# kinks_v41.net
KiCad netlist of a schematic drawn in EAGLE
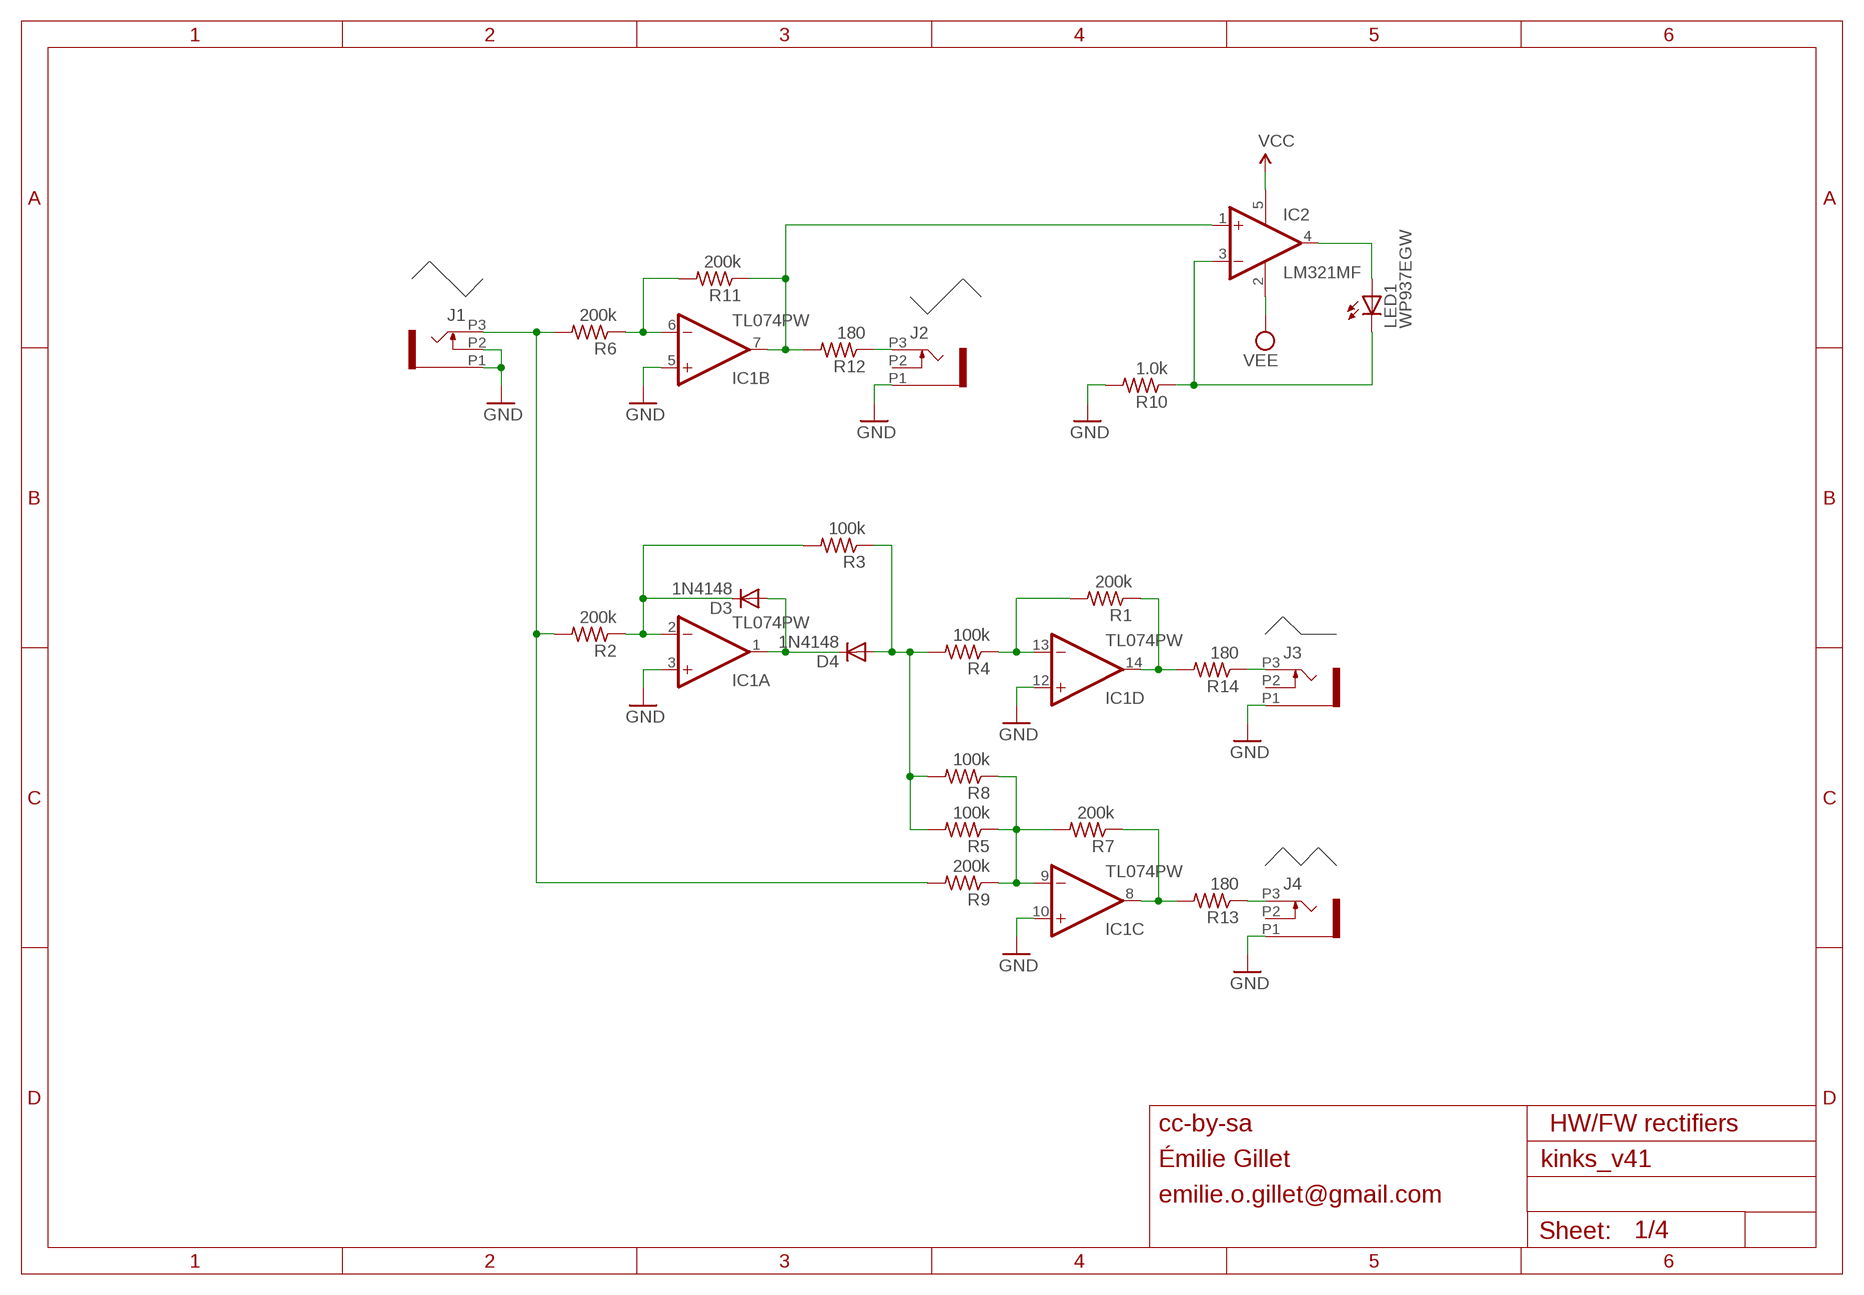
[diagram p0: schematic, sheet 1]
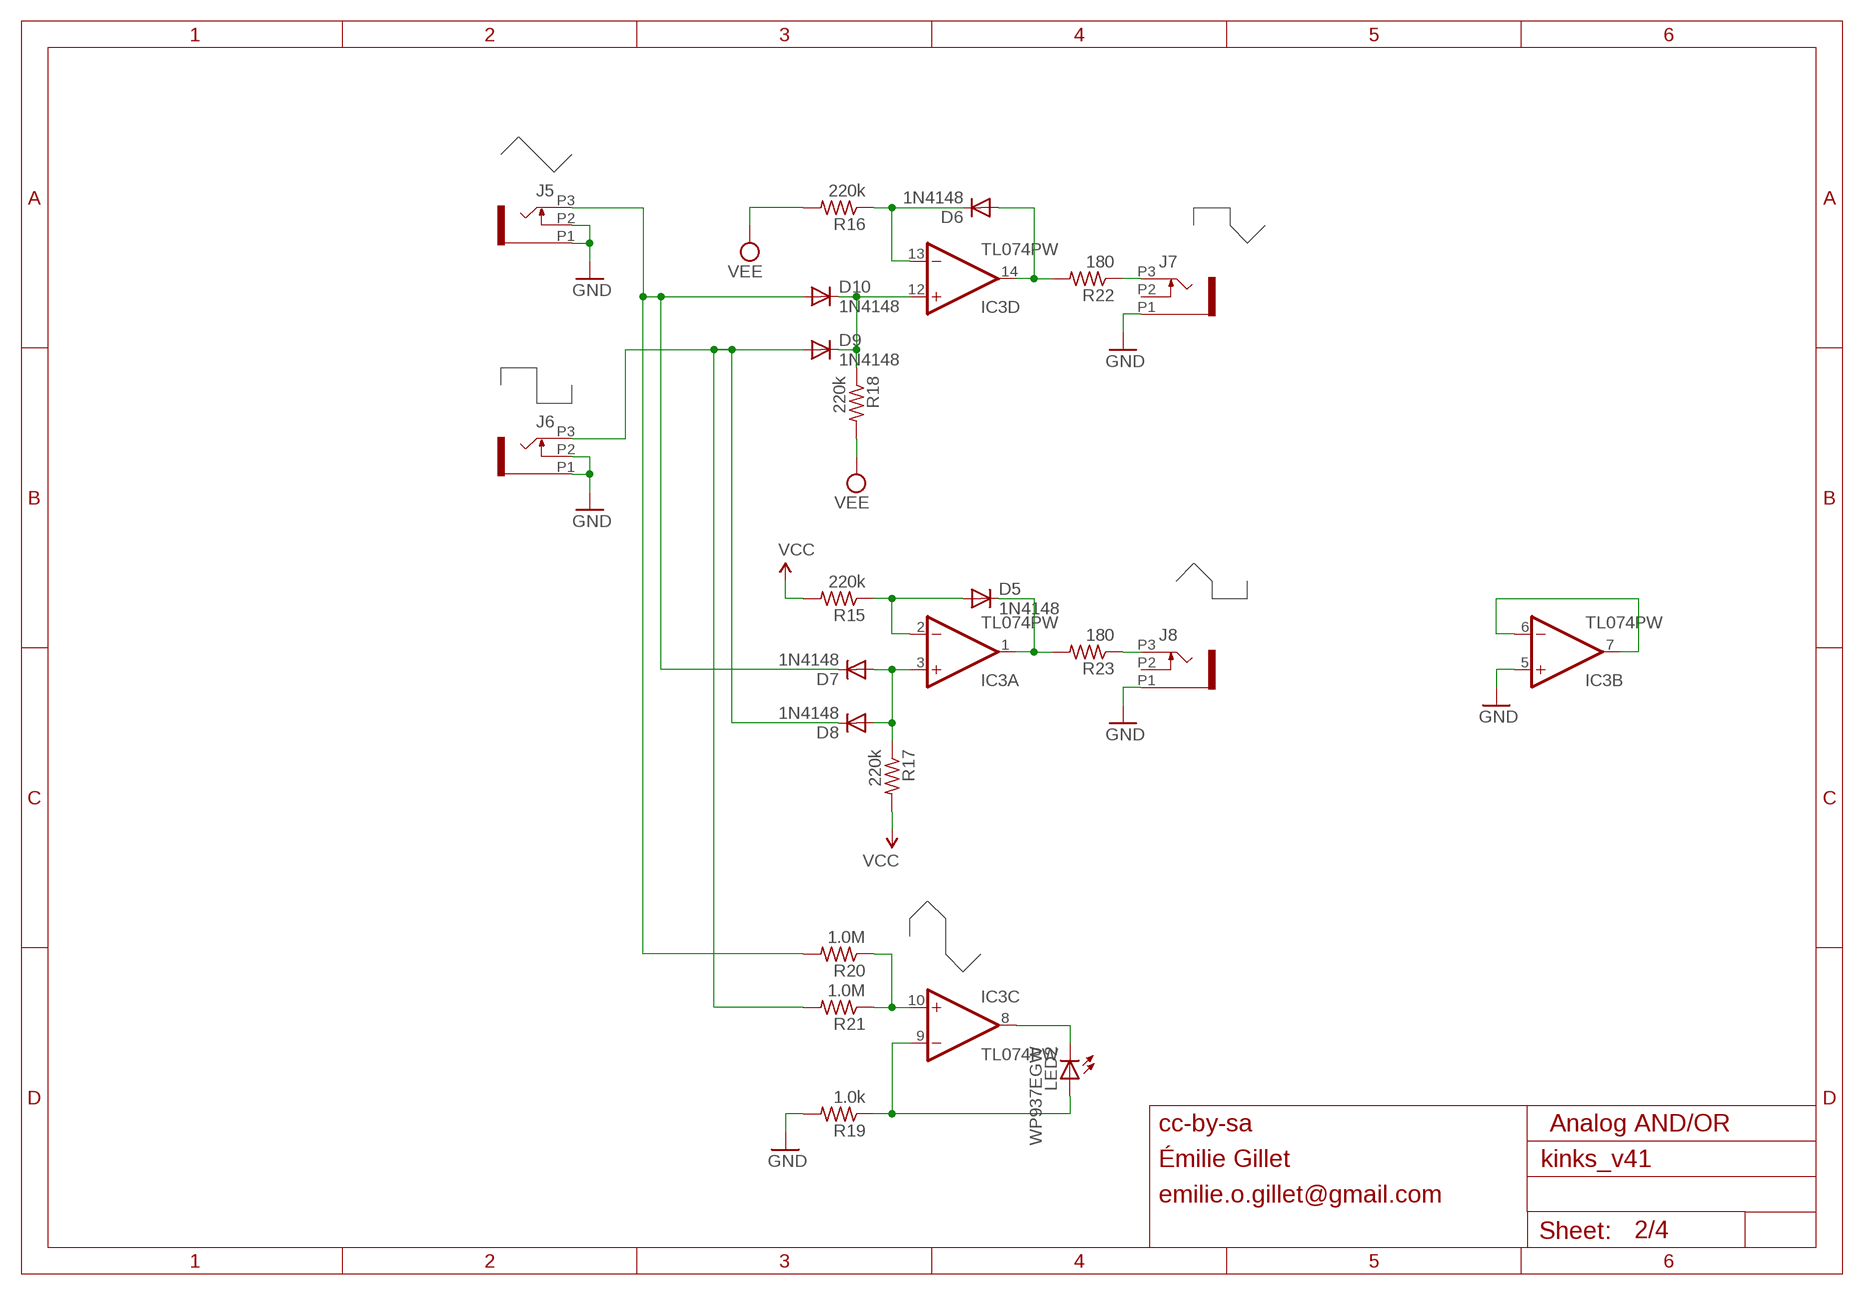
[diagram p1: schematic, sheet 2]
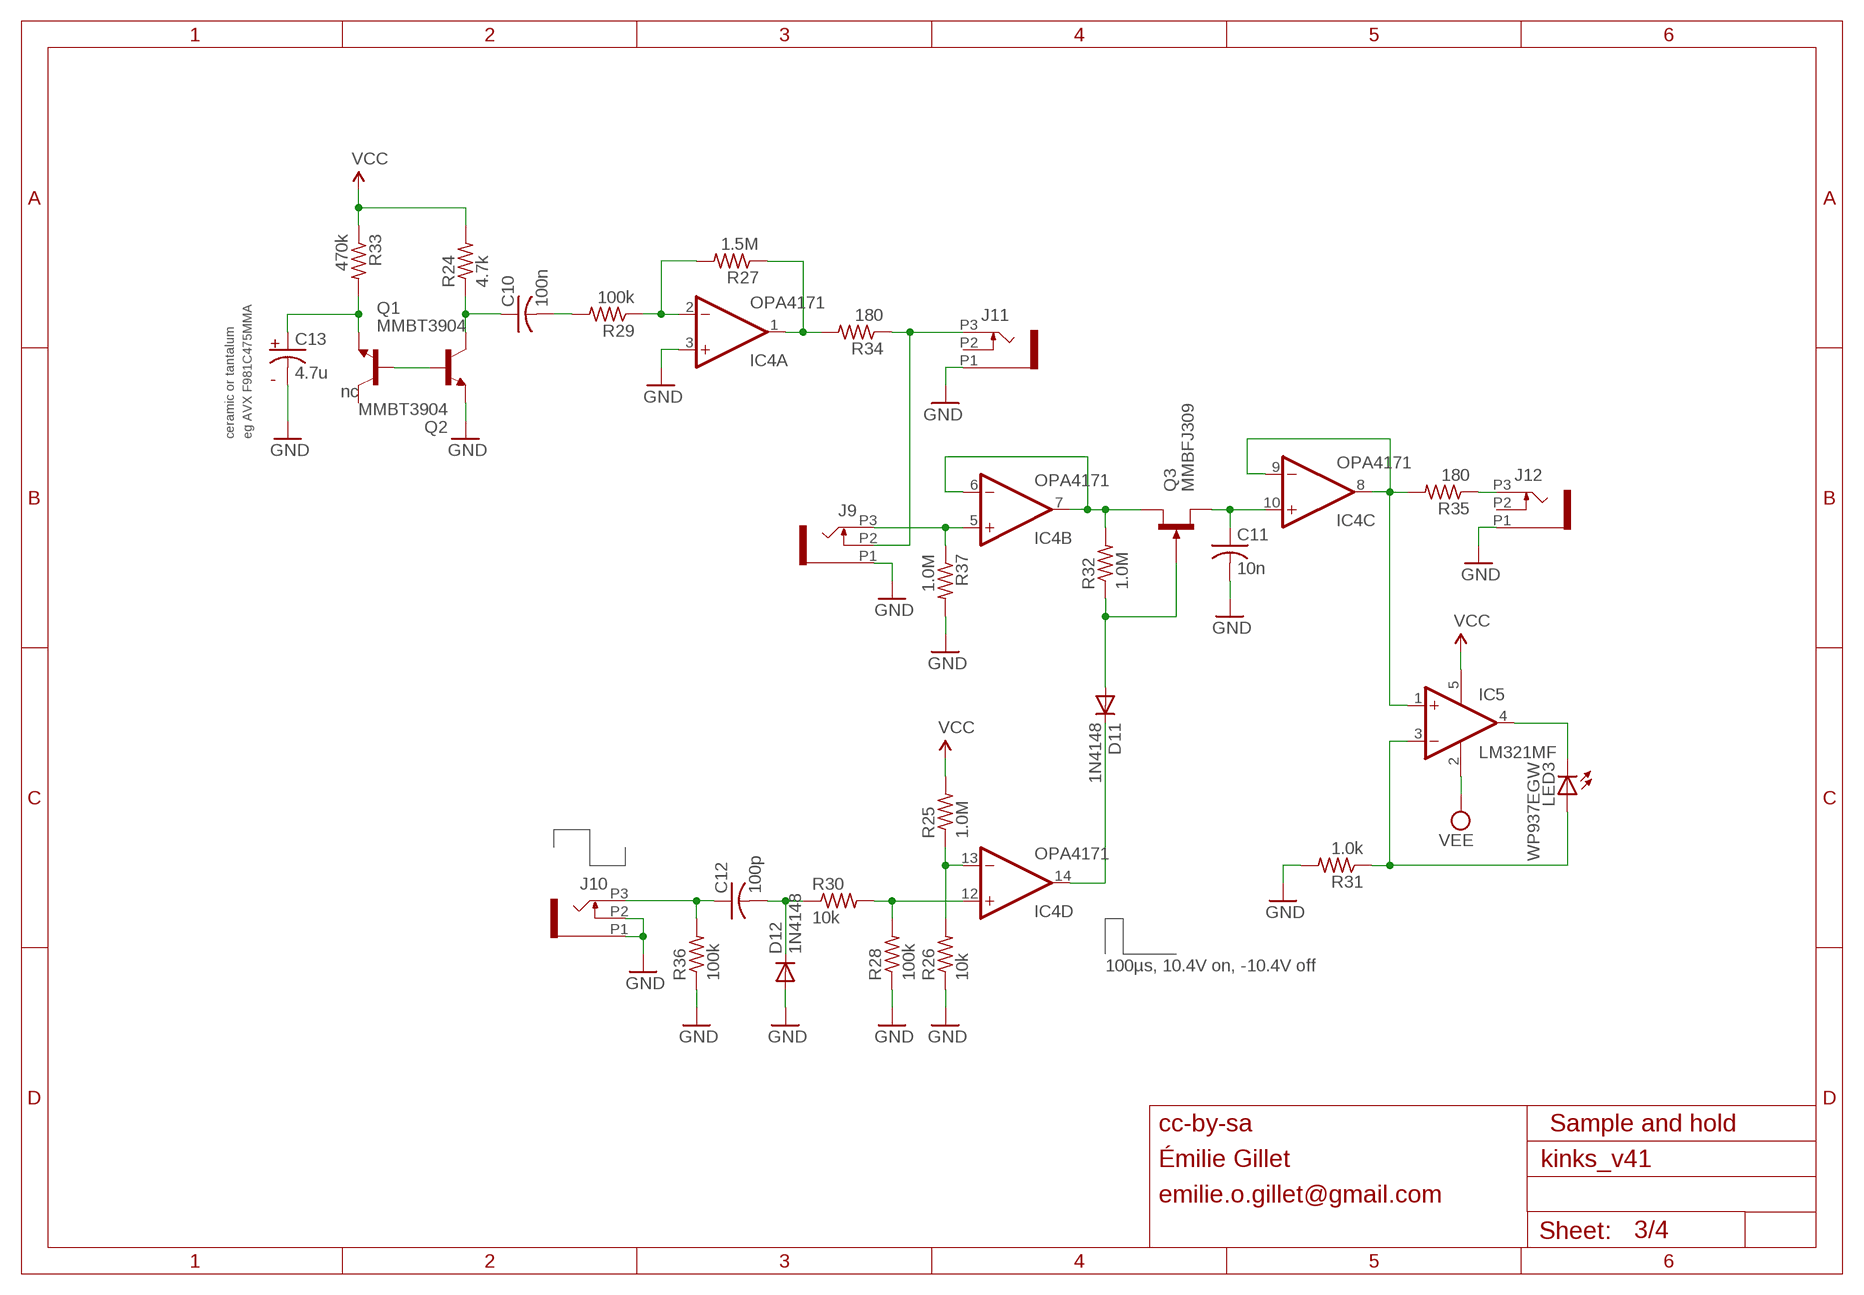
[diagram p2: schematic, sheet 3]
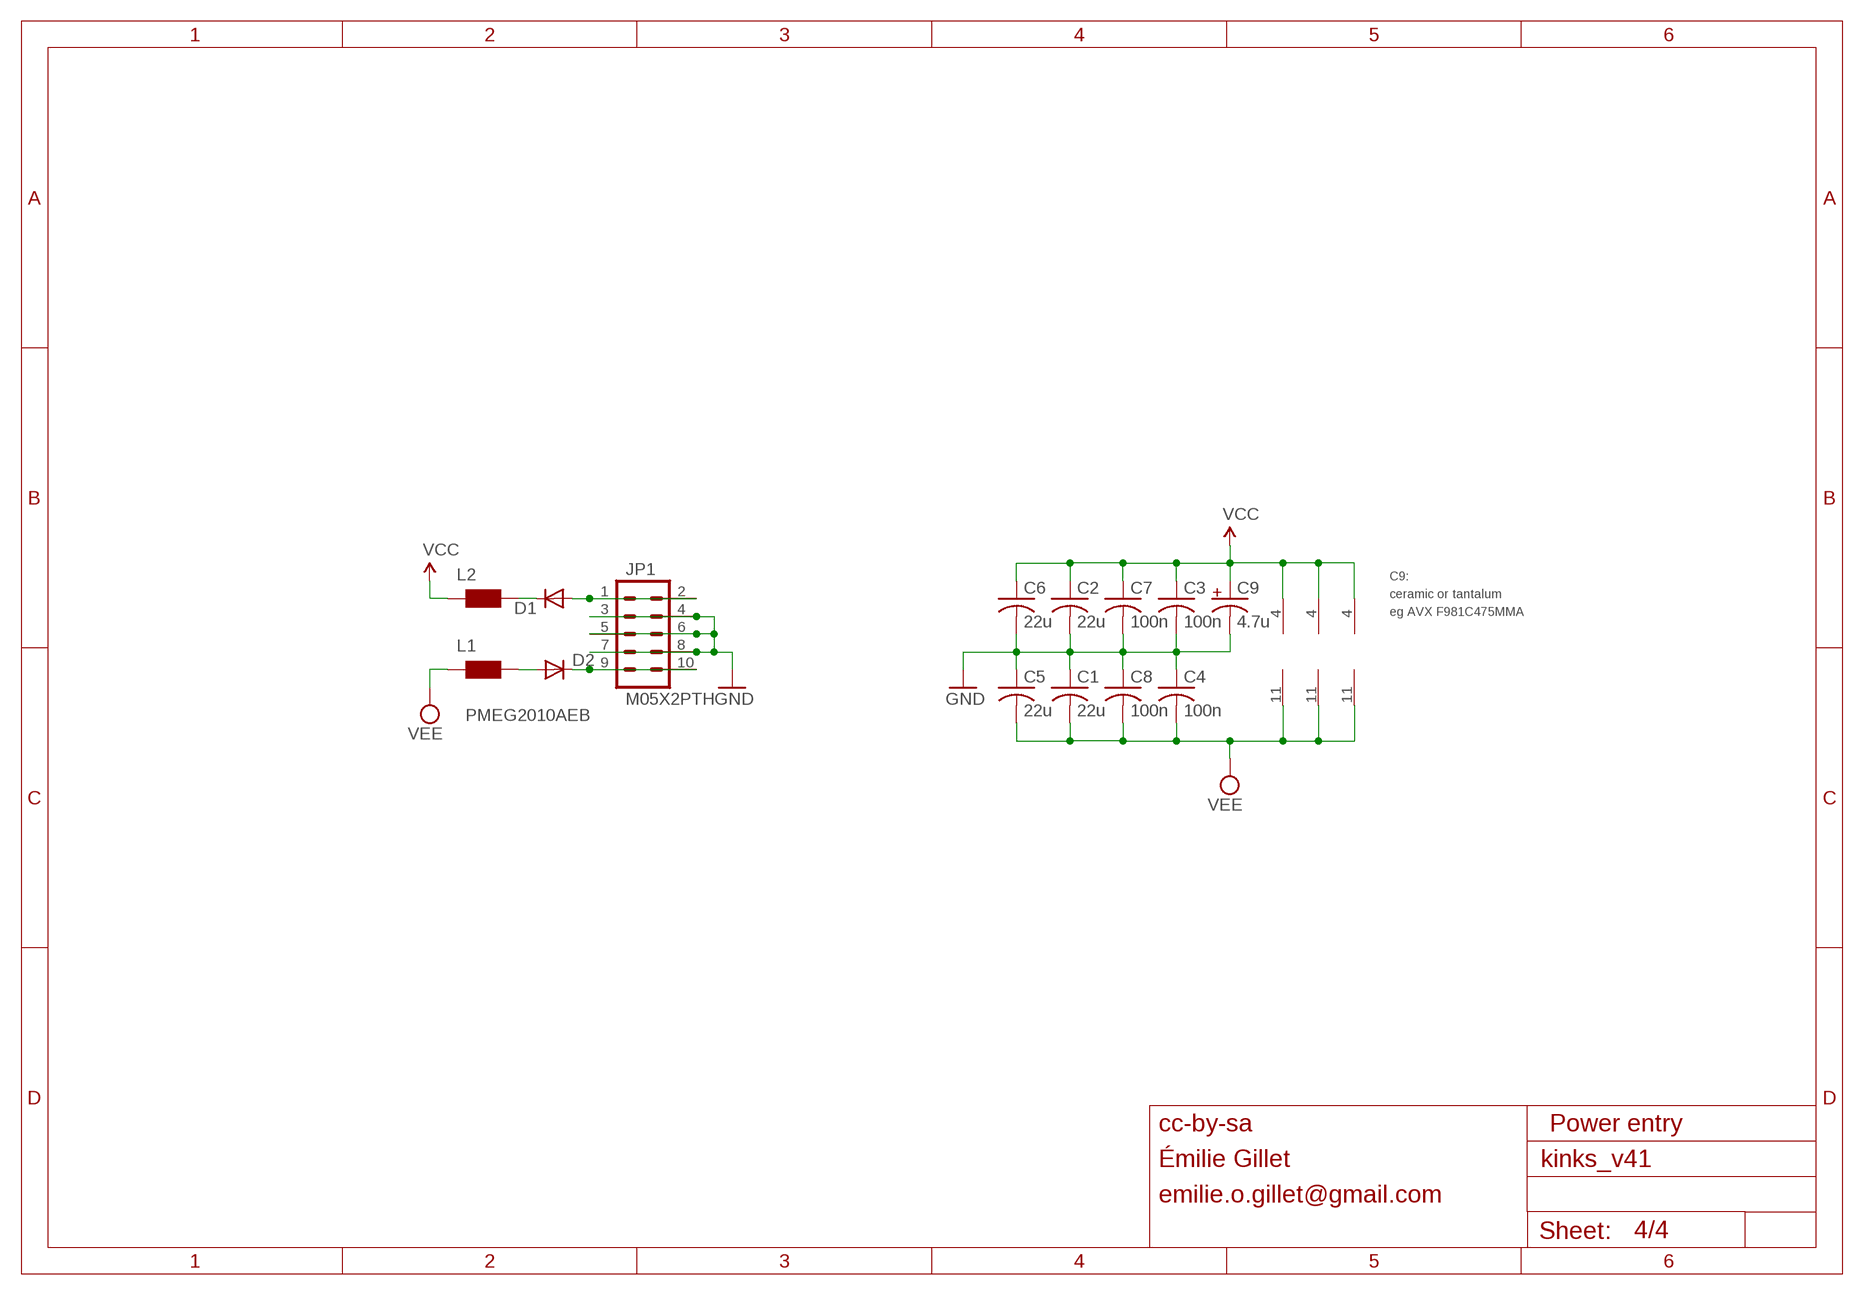
[diagram p3: schematic, sheet 4]

(export (version "E")
  (design (tool "Eeschema 10.0.6"))
  (components
    (comp (ref "D5")
      (value "1N4148")
      (footprint "eagle-import:SOD523")
      (libsource (lib "eagle-import") (part "DIODE-SOD523"))
    )
    (comp (ref "D6")
      (value "1N4148")
      (footprint "eagle-import:SOD523")
      (libsource (lib "eagle-import") (part "DIODE-SOD523"))
    )
    (comp (ref "D7")
      (value "1N4148")
      (footprint "eagle-import:SOD523")
      (libsource (lib "eagle-import") (part "DIODE-SOD523"))
    )
    (comp (ref "D8")
      (value "1N4148")
      (footprint "eagle-import:SOD523")
      (libsource (lib "eagle-import") (part "DIODE-SOD523"))
    )
    (comp (ref "D9")
      (value "1N4148")
      (footprint "eagle-import:SOD523")
      (libsource (lib "eagle-import") (part "DIODE-SOD523"))
    )
    (comp (ref "D10")
      (value "1N4148")
      (footprint "eagle-import:SOD523")
      (libsource (lib "eagle-import") (part "DIODE-SOD523"))
    )
    (comp (ref "IC3")
      (value "TL074PW")
      (footprint "eagle-import:TSSOP14")
      (libsource (lib "eagle-import") (part "TL074PW"))
    )
    (comp (ref "J5")
      (value "PJ301_THONKICONN6")
      (footprint "eagle-import:WQP_PJ_301M6")
      (libsource (lib "eagle-import") (part "PJ301_THONKICONN6"))
    )
    (comp (ref "J6")
      (value "PJ301_THONKICONN6")
      (footprint "eagle-import:WQP_PJ_301M6")
      (libsource (lib "eagle-import") (part "PJ301_THONKICONN6"))
    )
    (comp (ref "J7")
      (value "PJ301_THONKICONN6")
      (footprint "eagle-import:WQP_PJ_301M6")
      (libsource (lib "eagle-import") (part "PJ301_THONKICONN6"))
    )
    (comp (ref "J8")
      (value "PJ301_THONKICONN6")
      (footprint "eagle-import:WQP_PJ_301M6")
      (libsource (lib "eagle-import") (part "PJ301_THONKICONN6"))
    )
    (comp (ref "LED2")
      (value "WP937EGW")
      (footprint "eagle-import:LED3MM")
      (libsource (lib "eagle-import") (part "LED3MM"))
    )
    (comp (ref "R15")
      (value "220k")
      (footprint "eagle-import:R0402")
      (libsource (lib "eagle-import") (part "R-US_R0402"))
    )
    (comp (ref "R16")
      (value "220k")
      (footprint "eagle-import:R0402")
      (libsource (lib "eagle-import") (part "R-US_R0402"))
    )
    (comp (ref "R17")
      (value "220k")
      (footprint "eagle-import:R0402")
      (libsource (lib "eagle-import") (part "R-US_R0402"))
    )
    (comp (ref "R18")
      (value "220k")
      (footprint "eagle-import:R0402")
      (libsource (lib "eagle-import") (part "R-US_R0402"))
    )
    (comp (ref "R19")
      (value "1.0k")
      (footprint "eagle-import:R0402")
      (libsource (lib "eagle-import") (part "R-US_R0402"))
    )
    (comp (ref "R20")
      (value "1.0M")
      (footprint "eagle-import:R0402")
      (libsource (lib "eagle-import") (part "R-US_R0402"))
    )
    (comp (ref "R21")
      (value "1.0M")
      (footprint "eagle-import:R0402")
      (libsource (lib "eagle-import") (part "R-US_R0402"))
    )
    (comp (ref "R22")
      (value "180")
      (footprint "eagle-import:R0402")
      (libsource (lib "eagle-import") (part "R-US_R0402"))
    )
    (comp (ref "R23")
      (value "180")
      (footprint "eagle-import:R0402")
      (libsource (lib "eagle-import") (part "R-US_R0402"))
    )
    (comp (ref "C1")
      (value "22u")
      (footprint "eagle-import:C0805")
      (libsource (lib "eagle-import") (part "C-USC0805"))
    )
    (comp (ref "C2")
      (value "22u")
      (footprint "eagle-import:C0805")
      (libsource (lib "eagle-import") (part "C-USC0805"))
    )
    (comp (ref "C3")
      (value "100n")
      (footprint "eagle-import:C0402")
      (libsource (lib "eagle-import") (part "C-USC0402"))
    )
    (comp (ref "C4")
      (value "100n")
      (footprint "eagle-import:C0402")
      (libsource (lib "eagle-import") (part "C-USC0402"))
    )
    (comp (ref "C5")
      (value "22u")
      (footprint "eagle-import:C0805")
      (libsource (lib "eagle-import") (part "C-USC0805"))
    )
    (comp (ref "C6")
      (value "22u")
      (footprint "eagle-import:C0805")
      (libsource (lib "eagle-import") (part "C-USC0805"))
    )
    (comp (ref "C7")
      (value "100n")
      (footprint "eagle-import:C0402")
      (libsource (lib "eagle-import") (part "C-USC0402"))
    )
    (comp (ref "C8")
      (value "100n")
      (footprint "eagle-import:C0402")
      (libsource (lib "eagle-import") (part "C-USC0402"))
    )
    (comp (ref "C9")
      (value "4.7u")
      (footprint "eagle-import:C0603")
      (libsource (lib "eagle-import") (part "C-USC0603"))
    )
    (comp (ref "D1")
      (value "PMEG2010AEB")
      (footprint "eagle-import:SOD523")
      (libsource (lib "eagle-import") (part "DIODE-SOD523"))
    )
    (comp (ref "D2")
      (value "PMEG2010AEB")
      (footprint "eagle-import:SOD523")
      (libsource (lib "eagle-import") (part "DIODE-SOD523"))
    )
    (comp (ref "IC1")
      (value "TL074PW")
      (footprint "eagle-import:TSSOP14")
      (libsource (lib "eagle-import") (part "TL074PW"))
    )
    (comp (ref "IC4")
      (value "OPA4171")
      (footprint "eagle-import:TSSOP14")
      (libsource (lib "eagle-import") (part "TL074PW"))
    )
    (comp (ref "JP1")
      (value "M05X2PTH")
      (footprint "eagle-import:AVR_ICSP")
      (libsource (lib "eagle-import") (part "M05X2PTH"))
    )
    (comp (ref "L1")
      (value "WE-CBF_0603")
      (footprint "eagle-import:0603")
      (libsource (lib "eagle-import") (part "WE-CBF_0603"))
    )
    (comp (ref "L2")
      (value "WE-CBF_0603")
      (footprint "eagle-import:0603")
      (libsource (lib "eagle-import") (part "WE-CBF_0603"))
    )
    (comp (ref "D3")
      (value "1N4148")
      (footprint "eagle-import:SOD523")
      (libsource (lib "eagle-import") (part "DIODE-SOD523"))
    )
    (comp (ref "D4")
      (value "1N4148")
      (footprint "eagle-import:SOD523")
      (libsource (lib "eagle-import") (part "DIODE-SOD523"))
    )
    (comp (ref "IC2")
      (value "LM321MF")
      (footprint "eagle-import:SOT23-5")
      (libsource (lib "eagle-import") (part "LM321?MF"))
    )
    (comp (ref "J1")
      (value "PJ301_THONKICONN6")
      (footprint "eagle-import:WQP_PJ_301M6")
      (libsource (lib "eagle-import") (part "PJ301_THONKICONN6"))
    )
    (comp (ref "J2")
      (value "PJ301_THONKICONN6")
      (footprint "eagle-import:WQP_PJ_301M6")
      (libsource (lib "eagle-import") (part "PJ301_THONKICONN6"))
    )
    (comp (ref "J3")
      (value "PJ301_THONKICONN6")
      (footprint "eagle-import:WQP_PJ_301M6")
      (libsource (lib "eagle-import") (part "PJ301_THONKICONN6"))
    )
    (comp (ref "J4")
      (value "PJ301_THONKICONN6")
      (footprint "eagle-import:WQP_PJ_301M6")
      (libsource (lib "eagle-import") (part "PJ301_THONKICONN6"))
    )
    (comp (ref "LED1")
      (value "WP937EGW")
      (footprint "eagle-import:LED3MM")
      (libsource (lib "eagle-import") (part "LED3MM"))
    )
    (comp (ref "R1")
      (value "200k")
      (footprint "eagle-import:R0402")
      (libsource (lib "eagle-import") (part "R-US_R0402"))
    )
    (comp (ref "R2")
      (value "200k")
      (footprint "eagle-import:R0402")
      (libsource (lib "eagle-import") (part "R-US_R0402"))
    )
    (comp (ref "R3")
      (value "100k")
      (footprint "eagle-import:R0402")
      (libsource (lib "eagle-import") (part "R-US_R0402"))
    )
    (comp (ref "R4")
      (value "100k")
      (footprint "eagle-import:R0402")
      (libsource (lib "eagle-import") (part "R-US_R0402"))
    )
    (comp (ref "R5")
      (value "100k")
      (footprint "eagle-import:R0402")
      (libsource (lib "eagle-import") (part "R-US_R0402"))
    )
    (comp (ref "R6")
      (value "200k")
      (footprint "eagle-import:R0402")
      (libsource (lib "eagle-import") (part "R-US_R0402"))
    )
    (comp (ref "R7")
      (value "200k")
      (footprint "eagle-import:R0402")
      (libsource (lib "eagle-import") (part "R-US_R0402"))
    )
    (comp (ref "R8")
      (value "100k")
      (footprint "eagle-import:R0402")
      (libsource (lib "eagle-import") (part "R-US_R0402"))
    )
    (comp (ref "R9")
      (value "200k")
      (footprint "eagle-import:R0402")
      (libsource (lib "eagle-import") (part "R-US_R0402"))
    )
    (comp (ref "R10")
      (value "1.0k")
      (footprint "eagle-import:R0402")
      (libsource (lib "eagle-import") (part "R-US_R0402"))
    )
    (comp (ref "R11")
      (value "200k")
      (footprint "eagle-import:R0402")
      (libsource (lib "eagle-import") (part "R-US_R0402"))
    )
    (comp (ref "R12")
      (value "180")
      (footprint "eagle-import:R0402")
      (libsource (lib "eagle-import") (part "R-US_R0402"))
    )
    (comp (ref "R13")
      (value "180")
      (footprint "eagle-import:R0402")
      (libsource (lib "eagle-import") (part "R-US_R0402"))
    )
    (comp (ref "R14")
      (value "180")
      (footprint "eagle-import:R0402")
      (libsource (lib "eagle-import") (part "R-US_R0402"))
    )
    (comp (ref "C10")
      (value "100n")
      (footprint "eagle-import:C0402")
      (libsource (lib "eagle-import") (part "C-USC0402"))
    )
    (comp (ref "C11")
      (value "10n")
      (footprint "eagle-import:C0603")
      (libsource (lib "eagle-import") (part "C-USC0603"))
    )
    (comp (ref "C12")
      (value "100p")
      (footprint "eagle-import:C0402")
      (libsource (lib "eagle-import") (part "C-USC0402"))
    )
    (comp (ref "C13")
      (value "4.7u")
      (footprint "eagle-import:C0603")
      (libsource (lib "eagle-import") (part "C-USC0603"))
    )
    (comp (ref "D11")
      (value "1N4148")
      (footprint "eagle-import:SOD523")
      (libsource (lib "eagle-import") (part "DIODE-SOD523"))
    )
    (comp (ref "D12")
      (value "1N4148")
      (footprint "eagle-import:SOD523")
      (libsource (lib "eagle-import") (part "DIODE-SOD523"))
    )
    (comp (ref "IC5")
      (value "LM321MF")
      (footprint "eagle-import:SOT23-5")
      (libsource (lib "eagle-import") (part "LM321?MF"))
    )
    (comp (ref "J9")
      (value "PJ301_THONKICONN6")
      (footprint "eagle-import:WQP_PJ_301M6")
      (libsource (lib "eagle-import") (part "PJ301_THONKICONN6"))
    )
    (comp (ref "J10")
      (value "PJ301_THONKICONN6")
      (footprint "eagle-import:WQP_PJ_301M6")
      (libsource (lib "eagle-import") (part "PJ301_THONKICONN6"))
    )
    (comp (ref "J11")
      (value "PJ301_THONKICONN6")
      (footprint "eagle-import:WQP_PJ_301M6")
      (libsource (lib "eagle-import") (part "PJ301_THONKICONN6"))
    )
    (comp (ref "J12")
      (value "PJ301_THONKICONN6")
      (footprint "eagle-import:WQP_PJ_301M6")
      (libsource (lib "eagle-import") (part "PJ301_THONKICONN6"))
    )
    (comp (ref "LED3")
      (value "WP937EGW")
      (footprint "eagle-import:LED3MM")
      (libsource (lib "eagle-import") (part "LED3MM"))
    )
    (comp (ref "Q1")
      (value "MMBT3904")
      (footprint "eagle-import:SOT23-BEC")
      (libsource (lib "eagle-import") (part "-NPN-SOT23-BECMMBT3904LT1"))
    )
    (comp (ref "Q2")
      (value "MMBT3904")
      (footprint "eagle-import:SOT23-BEC")
      (libsource (lib "eagle-import") (part "-NPN-SOT23-BECMMBT3904LT1"))
    )
    (comp (ref "Q3")
      (value "MMBFJ309")
      (footprint "eagle-import:SOT23")
      (libsource (lib "eagle-import") (part "MMBFJ3"))
    )
    (comp (ref "R24")
      (value "4.7k")
      (footprint "eagle-import:R0402")
      (libsource (lib "eagle-import") (part "R-US_R0402"))
    )
    (comp (ref "R25")
      (value "1.0M")
      (footprint "eagle-import:R0402")
      (libsource (lib "eagle-import") (part "R-US_R0402"))
    )
    (comp (ref "R26")
      (value "10k")
      (footprint "eagle-import:R0402")
      (libsource (lib "eagle-import") (part "R-US_R0402"))
    )
    (comp (ref "R27")
      (value "1.5M")
      (footprint "eagle-import:R0402")
      (libsource (lib "eagle-import") (part "R-US_R0402"))
    )
    (comp (ref "R28")
      (value "100k")
      (footprint "eagle-import:R0402")
      (libsource (lib "eagle-import") (part "R-US_R0402"))
    )
    (comp (ref "R29")
      (value "100k")
      (footprint "eagle-import:R0402")
      (libsource (lib "eagle-import") (part "R-US_R0402"))
    )
    (comp (ref "R30")
      (value "10k")
      (footprint "eagle-import:R0402")
      (libsource (lib "eagle-import") (part "R-US_R0402"))
    )
    (comp (ref "R31")
      (value "1.0k")
      (footprint "eagle-import:R0402")
      (libsource (lib "eagle-import") (part "R-US_R0402"))
    )
    (comp (ref "R32")
      (value "1.0M")
      (footprint "eagle-import:R0402")
      (libsource (lib "eagle-import") (part "R-US_R0402"))
    )
    (comp (ref "R33")
      (value "470k")
      (footprint "eagle-import:R0402")
      (libsource (lib "eagle-import") (part "R-US_R0402"))
    )
    (comp (ref "R34")
      (value "180")
      (footprint "eagle-import:R0402")
      (libsource (lib "eagle-import") (part "R-US_R0402"))
    )
    (comp (ref "R35")
      (value "180")
      (footprint "eagle-import:R0402")
      (libsource (lib "eagle-import") (part "R-US_R0402"))
    )
    (comp (ref "R36")
      (value "100k")
      (footprint "eagle-import:R0402")
      (libsource (lib "eagle-import") (part "R-US_R0402"))
    )
    (comp (ref "R37")
      (value "1.0M")
      (footprint "eagle-import:R0402")
      (libsource (lib "eagle-import") (part "R-US_R0402"))
    )
  )
  (nets
    (net (code "1") (name "GND") (class "Default")
      (node (ref "C1") (pin "1") (pinfunction "1_1") (pintype "passive"))
      (node (ref "C11") (pin "2") (pinfunction "2_2") (pintype "passive"))
      (node (ref "C13") (pin "2") (pinfunction "2_2") (pintype "passive"))
      (node (ref "C2") (pin "2") (pinfunction "2_2") (pintype "passive"))
      (node (ref "C3") (pin "2") (pinfunction "2_2") (pintype "passive"))
      (node (ref "C4") (pin "1") (pinfunction "1_1") (pintype "passive"))
      (node (ref "C5") (pin "1") (pinfunction "1_1") (pintype "passive"))
      (node (ref "C6") (pin "2") (pinfunction "2_2") (pintype "passive"))
      (node (ref "C7") (pin "2") (pinfunction "2_2") (pintype "passive"))
      (node (ref "C8") (pin "1") (pinfunction "1_1") (pintype "passive"))
      (node (ref "C9") (pin "2") (pinfunction "2_2") (pintype "passive"))
      (node (ref "D12") (pin "A") (pinfunction "A_A") (pintype "passive"))
      (node (ref "IC1") (pin "10") (pinfunction "+IN_10") (pintype "input"))
      (node (ref "IC1") (pin "12") (pinfunction "+IN_12") (pintype "input"))
      (node (ref "IC1") (pin "3") (pinfunction "+IN_3") (pintype "input"))
      (node (ref "IC1") (pin "5") (pinfunction "+IN_5") (pintype "input"))
      (node (ref "IC3") (pin "5") (pinfunction "+IN_5") (pintype "input"))
      (node (ref "IC4") (pin "3") (pinfunction "+IN_3") (pintype "input"))
      (node (ref "J1") (pin "P1") (pinfunction "1_P1") (pintype "passive"))
      (node (ref "J1") (pin "P2") (pinfunction "2_P2") (pintype "passive"))
      (node (ref "J10") (pin "P1") (pinfunction "1_P1") (pintype "passive"))
      (node (ref "J10") (pin "P2") (pinfunction "2_P2") (pintype "passive"))
      (node (ref "J11") (pin "P1") (pinfunction "1_P1") (pintype "passive"))
      (node (ref "J12") (pin "P1") (pinfunction "1_P1") (pintype "passive"))
      (node (ref "J2") (pin "P1") (pinfunction "1_P1") (pintype "passive"))
      (node (ref "J3") (pin "P1") (pinfunction "1_P1") (pintype "passive"))
      (node (ref "J4") (pin "P1") (pinfunction "1_P1") (pintype "passive"))
      (node (ref "J5") (pin "P1") (pinfunction "1_P1") (pintype "passive"))
      (node (ref "J5") (pin "P2") (pinfunction "2_P2") (pintype "passive"))
      (node (ref "J6") (pin "P1") (pinfunction "1_P1") (pintype "passive"))
      (node (ref "J6") (pin "P2") (pinfunction "2_P2") (pintype "passive"))
      (node (ref "J7") (pin "P1") (pinfunction "1_P1") (pintype "passive"))
      (node (ref "J8") (pin "P1") (pinfunction "1_P1") (pintype "passive"))
      (node (ref "J9") (pin "P1") (pinfunction "1_P1") (pintype "passive"))
      (node (ref "JP1") (pin "3") (pinfunction "3_3") (pintype "passive"))
      (node (ref "JP1") (pin "4") (pinfunction "4_4") (pintype "passive"))
      (node (ref "JP1") (pin "5") (pinfunction "5_5") (pintype "passive"))
      (node (ref "JP1") (pin "6") (pinfunction "6_6") (pintype "passive"))
      (node (ref "JP1") (pin "7") (pinfunction "7_7") (pintype "passive"))
      (node (ref "JP1") (pin "8") (pinfunction "8_8") (pintype "passive"))
      (node (ref "Q1") (pin "E") (pinfunction "E_E") (pintype "passive"))
      (node (ref "R10") (pin "2") (pinfunction "2_2") (pintype "passive"))
      (node (ref "R19") (pin "2") (pinfunction "2_2") (pintype "passive"))
      (node (ref "R26") (pin "1") (pinfunction "1_1") (pintype "passive"))
      (node (ref "R28") (pin "1") (pinfunction "1_1") (pintype "passive"))
      (node (ref "R31") (pin "2") (pinfunction "2_2") (pintype "passive"))
      (node (ref "R36") (pin "1") (pinfunction "1_1") (pintype "passive"))
      (node (ref "R37") (pin "2") (pinfunction "2_2") (pintype "passive"))
    )
    (net (code "2") (name "Net-(C10-Pad1)") (class "Default")
      (node (ref "C10") (pin "1") (pinfunction "1_1") (pintype "passive"))
      (node (ref "Q1") (pin "C") (pinfunction "C_C") (pintype "passive"))
      (node (ref "R24") (pin "1") (pinfunction "1_1") (pintype "passive"))
    )
    (net (code "3") (name "Net-(C10-Pad2)") (class "Default")
      (node (ref "C10") (pin "2") (pinfunction "2_2") (pintype "passive"))
      (node (ref "R29") (pin "2") (pinfunction "2_2") (pintype "passive"))
    )
    (net (code "4") (name "Net-(C12-Pad2)") (class "Default")
      (node (ref "C12") (pin "2") (pinfunction "2_2") (pintype "passive"))
      (node (ref "D12") (pin "C") (pinfunction "C_C") (pintype "passive"))
      (node (ref "R30") (pin "1") (pinfunction "1_1") (pintype "passive"))
    )
    (net (code "5") (name "Net-(C13-Pad1)") (class "Default")
      (node (ref "C13") (pin "1") (pinfunction "1_1") (pintype "passive"))
      (node (ref "Q2") (pin "E") (pinfunction "E_E") (pintype "passive"))
      (node (ref "R33") (pin "2") (pinfunction "2_2") (pintype "passive"))
    )
    (net (code "6") (name "Net-(D1-PadA)") (class "Default")
      (node (ref "D1") (pin "A") (pinfunction "A_A") (pintype "passive"))
      (node (ref "JP1") (pin "1") (pinfunction "1_1") (pintype "passive"))
      (node (ref "JP1") (pin "2") (pinfunction "2_2") (pintype "passive"))
    )
    (net (code "7") (name "Net-(D1-PadC)") (class "Default")
      (node (ref "D1") (pin "C") (pinfunction "C_C") (pintype "passive"))
      (node (ref "L2") (pin "2") (pinfunction "2_2") (pintype "passive"))
    )
    (net (code "8") (name "Net-(D2-PadA)") (class "Default")
      (node (ref "D2") (pin "A") (pinfunction "A_A") (pintype "passive"))
      (node (ref "L1") (pin "2") (pinfunction "2_2") (pintype "passive"))
    )
    (net (code "9") (name "Net-(D2-PadC)") (class "Default")
      (node (ref "D2") (pin "C") (pinfunction "C_C") (pintype "passive"))
      (node (ref "JP1") (pin "10") (pinfunction "10_10") (pintype "passive"))
      (node (ref "JP1") (pin "9") (pinfunction "9_9") (pintype "passive"))
    )
    (net (code "10") (name "Net-(D4-PadA)") (class "Default")
      (node (ref "D4") (pin "A") (pinfunction "A_A") (pintype "passive"))
      (node (ref "R3") (pin "1") (pinfunction "1_1") (pintype "passive"))
      (node (ref "R4") (pin "2") (pinfunction "2_2") (pintype "passive"))
      (node (ref "R5") (pin "2") (pinfunction "2_2") (pintype "passive"))
      (node (ref "R8") (pin "2") (pinfunction "2_2") (pintype "passive"))
    )
    (net (code "11") (name "Net-(IC1A--IN)") (class "Default")
      (node (ref "D3") (pin "C") (pinfunction "C_C") (pintype "passive"))
      (node (ref "IC1") (pin "2") (pinfunction "-IN_2") (pintype "input"))
      (node (ref "R2") (pin "1") (pinfunction "1_1") (pintype "passive"))
      (node (ref "R3") (pin "2") (pinfunction "2_2") (pintype "passive"))
    )
    (net (code "12") (name "Net-(IC1A-OUT)") (class "Default")
      (node (ref "D3") (pin "A") (pinfunction "A_A") (pintype "passive"))
      (node (ref "D4") (pin "C") (pinfunction "C_C") (pintype "passive"))
      (node (ref "IC1") (pin "1") (pinfunction "OUT_1") (pintype "output"))
    )
    (net (code "13") (name "Net-(IC1B--IN)") (class "Default")
      (node (ref "IC1") (pin "6") (pinfunction "-IN_6") (pintype "input"))
      (node (ref "R11") (pin "2") (pinfunction "2_2") (pintype "passive"))
      (node (ref "R6") (pin "1") (pinfunction "1_1") (pintype "passive"))
    )
    (net (code "14") (name "Net-(IC1B-OUT)") (class "Default")
      (node (ref "IC1") (pin "7") (pinfunction "OUT_7") (pintype "output"))
      (node (ref "IC2") (pin "1") (pinfunction "+IN_1") (pintype "input"))
      (node (ref "R11") (pin "1") (pinfunction "1_1") (pintype "passive"))
      (node (ref "R12") (pin "2") (pinfunction "2_2") (pintype "passive"))
    )
    (net (code "15") (name "Net-(IC1C--IN)") (class "Default")
      (node (ref "IC1") (pin "9") (pinfunction "-IN_9") (pintype "input"))
      (node (ref "R5") (pin "1") (pinfunction "1_1") (pintype "passive"))
      (node (ref "R7") (pin "2") (pinfunction "2_2") (pintype "passive"))
      (node (ref "R8") (pin "1") (pinfunction "1_1") (pintype "passive"))
      (node (ref "R9") (pin "1") (pinfunction "1_1") (pintype "passive"))
    )
    (net (code "16") (name "Net-(IC1C-OUT)") (class "Default")
      (node (ref "IC1") (pin "8") (pinfunction "OUT_8") (pintype "output"))
      (node (ref "R13") (pin "2") (pinfunction "2_2") (pintype "passive"))
      (node (ref "R7") (pin "1") (pinfunction "1_1") (pintype "passive"))
    )
    (net (code "17") (name "Net-(IC1D--IN)") (class "Default")
      (node (ref "IC1") (pin "13") (pinfunction "-IN_13") (pintype "input"))
      (node (ref "R1") (pin "2") (pinfunction "2_2") (pintype "passive"))
      (node (ref "R4") (pin "1") (pinfunction "1_1") (pintype "passive"))
    )
    (net (code "18") (name "Net-(IC1D-OUT)") (class "Default")
      (node (ref "IC1") (pin "14") (pinfunction "OUT_14") (pintype "output"))
      (node (ref "R1") (pin "1") (pinfunction "1_1") (pintype "passive"))
      (node (ref "R14") (pin "2") (pinfunction "2_2") (pintype "passive"))
    )
    (net (code "19") (name "Net-(IC2--IN)") (class "Default")
      (node (ref "IC2") (pin "3") (pinfunction "-IN_3") (pintype "input"))
      (node (ref "LED1") (pin "K") (pinfunction "C_K") (pintype "passive"))
      (node (ref "R10") (pin "1") (pinfunction "1_1") (pintype "passive"))
    )
    (net (code "20") (name "Net-(IC2-OUT)") (class "Default")
      (node (ref "IC2") (pin "4") (pinfunction "OUT_4") (pintype "output"))
      (node (ref "LED1") (pin "A") (pinfunction "A_A") (pintype "passive"))
    )
    (net (code "21") (name "Net-(IC3A-+IN)") (class "Default")
      (node (ref "D7") (pin "A") (pinfunction "A_A") (pintype "passive"))
      (node (ref "D8") (pin "A") (pinfunction "A_A") (pintype "passive"))
      (node (ref "IC3") (pin "3") (pinfunction "+IN_3") (pintype "input"))
      (node (ref "R17") (pin "1") (pinfunction "1_1") (pintype "passive"))
    )
    (net (code "22") (name "Net-(IC3A--IN)") (class "Default")
      (node (ref "D5") (pin "A") (pinfunction "A_A") (pintype "passive"))
      (node (ref "IC3") (pin "2") (pinfunction "-IN_2") (pintype "input"))
      (node (ref "R15") (pin "1") (pinfunction "1_1") (pintype "passive"))
    )
    (net (code "23") (name "Net-(IC3A-OUT)") (class "Default")
      (node (ref "D5") (pin "C") (pinfunction "C_C") (pintype "passive"))
      (node (ref "IC3") (pin "1") (pinfunction "OUT_1") (pintype "output"))
      (node (ref "R23") (pin "2") (pinfunction "2_2") (pintype "passive"))
    )
    (net (code "24") (name "Net-(IC3B--IN)") (class "Default")
      (node (ref "IC3") (pin "6") (pinfunction "-IN_6") (pintype "input"))
      (node (ref "IC3") (pin "7") (pinfunction "OUT_7") (pintype "output"))
    )
    (net (code "25") (name "Net-(IC3C-+IN)") (class "Default")
      (node (ref "IC3") (pin "10") (pinfunction "+IN_10") (pintype "input"))
      (node (ref "R20") (pin "1") (pinfunction "1_1") (pintype "passive"))
      (node (ref "R21") (pin "1") (pinfunction "1_1") (pintype "passive"))
    )
    (net (code "26") (name "Net-(IC3C--IN)") (class "Default")
      (node (ref "IC3") (pin "9") (pinfunction "-IN_9") (pintype "input"))
      (node (ref "LED2") (pin "A") (pinfunction "A_A") (pintype "passive"))
      (node (ref "R19") (pin "1") (pinfunction "1_1") (pintype "passive"))
    )
    (net (code "27") (name "Net-(IC3C-OUT)") (class "Default")
      (node (ref "IC3") (pin "8") (pinfunction "OUT_8") (pintype "output"))
      (node (ref "LED2") (pin "K") (pinfunction "C_K") (pintype "passive"))
    )
    (net (code "28") (name "Net-(IC3D-+IN)") (class "Default")
      (node (ref "D10") (pin "C") (pinfunction "C_C") (pintype "passive"))
      (node (ref "D9") (pin "C") (pinfunction "C_C") (pintype "passive"))
      (node (ref "IC3") (pin "12") (pinfunction "+IN_12") (pintype "input"))
      (node (ref "R18") (pin "1") (pinfunction "1_1") (pintype "passive"))
    )
    (net (code "29") (name "Net-(IC3D--IN)") (class "Default")
      (node (ref "D6") (pin "C") (pinfunction "C_C") (pintype "passive"))
      (node (ref "IC3") (pin "13") (pinfunction "-IN_13") (pintype "input"))
      (node (ref "R16") (pin "1") (pinfunction "1_1") (pintype "passive"))
    )
    (net (code "30") (name "Net-(IC3D-OUT)") (class "Default")
      (node (ref "D6") (pin "A") (pinfunction "A_A") (pintype "passive"))
      (node (ref "IC3") (pin "14") (pinfunction "OUT_14") (pintype "output"))
      (node (ref "R22") (pin "2") (pinfunction "2_2") (pintype "passive"))
    )
    (net (code "31") (name "Net-(IC4A--IN)") (class "Default")
      (node (ref "IC4") (pin "2") (pinfunction "-IN_2") (pintype "input"))
      (node (ref "R27") (pin "2") (pinfunction "2_2") (pintype "passive"))
      (node (ref "R29") (pin "1") (pinfunction "1_1") (pintype "passive"))
    )
    (net (code "32") (name "Net-(IC4A-OUT)") (class "Default")
      (node (ref "IC4") (pin "1") (pinfunction "OUT_1") (pintype "output"))
      (node (ref "R27") (pin "1") (pinfunction "1_1") (pintype "passive"))
      (node (ref "R34") (pin "2") (pinfunction "2_2") (pintype "passive"))
    )
    (net (code "33") (name "Net-(IC4B-+IN)") (class "Default")
      (node (ref "IC4") (pin "5") (pinfunction "+IN_5") (pintype "input"))
      (node (ref "J9") (pin "P3") (pinfunction "3_P3") (pintype "passive"))
      (node (ref "R37") (pin "1") (pinfunction "1_1") (pintype "passive"))
    )
    (net (code "34") (name "Net-(IC4B--IN)") (class "Default")
      (node (ref "IC4") (pin "6") (pinfunction "-IN_6") (pintype "input"))
      (node (ref "IC4") (pin "7") (pinfunction "OUT_7") (pintype "output"))
      (node (ref "Q3") (pin "1") (pinfunction "D_1") (pintype "passive"))
      (node (ref "R32") (pin "2") (pinfunction "2_2") (pintype "passive"))
    )
    (net (code "35") (name "Net-(IC4C-+IN)") (class "Default")
      (node (ref "C11") (pin "1") (pinfunction "1_1") (pintype "passive"))
      (node (ref "IC4") (pin "10") (pinfunction "+IN_10") (pintype "input"))
      (node (ref "Q3") (pin "2") (pinfunction "S_2") (pintype "passive"))
    )
    (net (code "36") (name "Net-(IC4C--IN)") (class "Default")
      (node (ref "IC4") (pin "8") (pinfunction "OUT_8") (pintype "output"))
      (node (ref "IC4") (pin "9") (pinfunction "-IN_9") (pintype "input"))
      (node (ref "IC5") (pin "1") (pinfunction "+IN_1") (pintype "input"))
      (node (ref "R35") (pin "2") (pinfunction "2_2") (pintype "passive"))
    )
    (net (code "37") (name "Net-(IC4D-+IN)") (class "Default")
      (node (ref "IC4") (pin "12") (pinfunction "+IN_12") (pintype "input"))
      (node (ref "R28") (pin "2") (pinfunction "2_2") (pintype "passive"))
      (node (ref "R30") (pin "2") (pinfunction "2_2") (pintype "passive"))
    )
    (net (code "38") (name "Net-(IC4D--IN)") (class "Default")
      (node (ref "IC4") (pin "13") (pinfunction "-IN_13") (pintype "input"))
      (node (ref "R25") (pin "1") (pinfunction "1_1") (pintype "passive"))
      (node (ref "R26") (pin "2") (pinfunction "2_2") (pintype "passive"))
    )
    (net (code "39") (name "Net-(IC4D-OUT)") (class "Default")
      (node (ref "D11") (pin "C") (pinfunction "C_C") (pintype "passive"))
      (node (ref "IC4") (pin "14") (pinfunction "OUT_14") (pintype "output"))
    )
    (net (code "40") (name "Net-(IC5--IN)") (class "Default")
      (node (ref "IC5") (pin "3") (pinfunction "-IN_3") (pintype "input"))
      (node (ref "LED3") (pin "A") (pinfunction "A_A") (pintype "passive"))
      (node (ref "R31") (pin "1") (pinfunction "1_1") (pintype "passive"))
    )
    (net (code "41") (name "Net-(IC5-OUT)") (class "Default")
      (node (ref "IC5") (pin "4") (pinfunction "OUT_4") (pintype "output"))
      (node (ref "LED3") (pin "K") (pinfunction "C_K") (pintype "passive"))
    )
    (net (code "42") (name "Net-(J1-3)") (class "Default")
      (node (ref "J1") (pin "P3") (pinfunction "3_P3") (pintype "passive"))
      (node (ref "R2") (pin "2") (pinfunction "2_2") (pintype "passive"))
      (node (ref "R6") (pin "2") (pinfunction "2_2") (pintype "passive"))
      (node (ref "R9") (pin "2") (pinfunction "2_2") (pintype "passive"))
    )
    (net (code "43") (name "Net-(J2-3)") (class "Default")
      (node (ref "J2") (pin "P3") (pinfunction "3_P3") (pintype "passive"))
      (node (ref "R12") (pin "1") (pinfunction "1_1") (pintype "passive"))
    )
    (net (code "44") (name "Net-(J3-3)") (class "Default")
      (node (ref "J3") (pin "P3") (pinfunction "3_P3") (pintype "passive"))
      (node (ref "R14") (pin "1") (pinfunction "1_1") (pintype "passive"))
    )
    (net (code "45") (name "Net-(J4-3)") (class "Default")
      (node (ref "J4") (pin "P3") (pinfunction "3_P3") (pintype "passive"))
      (node (ref "R13") (pin "1") (pinfunction "1_1") (pintype "passive"))
    )
    (net (code "46") (name "Net-(J5-3)") (class "Default")
      (node (ref "D10") (pin "A") (pinfunction "A_A") (pintype "passive"))
      (node (ref "D7") (pin "C") (pinfunction "C_C") (pintype "passive"))
      (node (ref "J5") (pin "P3") (pinfunction "3_P3") (pintype "passive"))
      (node (ref "R20") (pin "2") (pinfunction "2_2") (pintype "passive"))
    )
    (net (code "47") (name "Net-(J6-3)") (class "Default")
      (node (ref "D8") (pin "C") (pinfunction "C_C") (pintype "passive"))
      (node (ref "D9") (pin "A") (pinfunction "A_A") (pintype "passive"))
      (node (ref "J6") (pin "P3") (pinfunction "3_P3") (pintype "passive"))
      (node (ref "R21") (pin "2") (pinfunction "2_2") (pintype "passive"))
    )
    (net (code "48") (name "Net-(J7-3)") (class "Default")
      (node (ref "J7") (pin "P3") (pinfunction "3_P3") (pintype "passive"))
      (node (ref "R22") (pin "1") (pinfunction "1_1") (pintype "passive"))
    )
    (net (code "49") (name "Net-(J8-3)") (class "Default")
      (node (ref "J8") (pin "P3") (pinfunction "3_P3") (pintype "passive"))
      (node (ref "R23") (pin "1") (pinfunction "1_1") (pintype "passive"))
    )
    (net (code "50") (name "Net-(J10-3)") (class "Default")
      (node (ref "C12") (pin "1") (pinfunction "1_1") (pintype "passive"))
      (node (ref "J10") (pin "P3") (pinfunction "3_P3") (pintype "passive"))
      (node (ref "R36") (pin "2") (pinfunction "2_2") (pintype "passive"))
    )
    (net (code "51") (name "Net-(J11-3)") (class "Default")
      (node (ref "J11") (pin "P3") (pinfunction "3_P3") (pintype "passive"))
      (node (ref "J9") (pin "P2") (pinfunction "2_P2") (pintype "passive"))
      (node (ref "R34") (pin "1") (pinfunction "1_1") (pintype "passive"))
    )
    (net (code "52") (name "Net-(J12-3)") (class "Default")
      (node (ref "J12") (pin "P3") (pinfunction "3_P3") (pintype "passive"))
      (node (ref "R35") (pin "1") (pinfunction "1_1") (pintype "passive"))
    )
    (net (code "53") (name "Net-(Q1-PadB)") (class "Default")
      (node (ref "Q1") (pin "B") (pinfunction "B_B") (pintype "passive"))
      (node (ref "Q2") (pin "B") (pinfunction "B_B") (pintype "passive"))
    )
    (net (code "54") (name "Net-(Q3-G)") (class "Default")
      (node (ref "D11") (pin "A") (pinfunction "A_A") (pintype "passive"))
      (node (ref "Q3") (pin "3") (pinfunction "G_3") (pintype "passive"))
      (node (ref "R32") (pin "1") (pinfunction "1_1") (pintype "passive"))
    )
    (net (code "55") (name "VCC") (class "Default")
      (node (ref "C2") (pin "1") (pinfunction "1_1") (pintype "passive"))
      (node (ref "C3") (pin "1") (pinfunction "1_1") (pintype "passive"))
      (node (ref "C6") (pin "1") (pinfunction "1_1") (pintype "passive"))
      (node (ref "C7") (pin "1") (pinfunction "1_1") (pintype "passive"))
      (node (ref "C9") (pin "1") (pinfunction "1_1") (pintype "passive"))
      (node (ref "IC1") (pin "4") (pinfunction "V+_4") (pintype "power_in"))
      (node (ref "IC2") (pin "5") (pinfunction "V+_5") (pintype "power_in"))
      (node (ref "IC3") (pin "4") (pinfunction "V+_4") (pintype "power_in"))
      (node (ref "IC4") (pin "4") (pinfunction "V+_4") (pintype "power_in"))
      (node (ref "IC5") (pin "5") (pinfunction "V+_5") (pintype "power_in"))
      (node (ref "L2") (pin "1") (pinfunction "1_1") (pintype "passive"))
      (node (ref "R15") (pin "2") (pinfunction "2_2") (pintype "passive"))
      (node (ref "R17") (pin "2") (pinfunction "2_2") (pintype "passive"))
      (node (ref "R24") (pin "2") (pinfunction "2_2") (pintype "passive"))
      (node (ref "R25") (pin "2") (pinfunction "2_2") (pintype "passive"))
      (node (ref "R33") (pin "1") (pinfunction "1_1") (pintype "passive"))
    )
    (net (code "56") (name "VEE") (class "Default")
      (node (ref "C1") (pin "2") (pinfunction "2_2") (pintype "passive"))
      (node (ref "C4") (pin "2") (pinfunction "2_2") (pintype "passive"))
      (node (ref "C5") (pin "2") (pinfunction "2_2") (pintype "passive"))
      (node (ref "C8") (pin "2") (pinfunction "2_2") (pintype "passive"))
      (node (ref "IC1") (pin "11") (pinfunction "V-_11") (pintype "power_in"))
      (node (ref "IC2") (pin "2") (pinfunction "V-_2") (pintype "power_in"))
      (node (ref "IC3") (pin "11") (pinfunction "V-_11") (pintype "power_in"))
      (node (ref "IC4") (pin "11") (pinfunction "V-_11") (pintype "power_in"))
      (node (ref "IC5") (pin "2") (pinfunction "V-_2") (pintype "power_in"))
      (node (ref "L1") (pin "1") (pinfunction "1_1") (pintype "passive"))
      (node (ref "R16") (pin "2") (pinfunction "2_2") (pintype "passive"))
      (node (ref "R18") (pin "2") (pinfunction "2_2") (pintype "passive"))
    )
    (net (code "57") (name "unconnected-(J2-2-PadP2)") (class "Default")
      (node (ref "J2") (pin "P2") (pinfunction "2_P2") (pintype "passive"))
    )
    (net (code "58") (name "unconnected-(J3-2-PadP2)") (class "Default")
      (node (ref "J3") (pin "P2") (pinfunction "2_P2") (pintype "passive"))
    )
    (net (code "59") (name "unconnected-(J4-2-PadP2)") (class "Default")
      (node (ref "J4") (pin "P2") (pinfunction "2_P2") (pintype "passive"))
    )
    (net (code "60") (name "unconnected-(J7-2-PadP2)") (class "Default")
      (node (ref "J7") (pin "P2") (pinfunction "2_P2") (pintype "passive"))
    )
    (net (code "61") (name "unconnected-(J8-2-PadP2)") (class "Default")
      (node (ref "J8") (pin "P2") (pinfunction "2_P2") (pintype "passive"))
    )
    (net (code "62") (name "unconnected-(J11-2-PadP2)") (class "Default")
      (node (ref "J11") (pin "P2") (pinfunction "2_P2") (pintype "passive"))
    )
    (net (code "63") (name "unconnected-(J12-2-PadP2)") (class "Default")
      (node (ref "J12") (pin "P2") (pinfunction "2_P2") (pintype "passive"))
    )
    (net (code "64") (name "unconnected-(Q2-PadC)") (class "Default")
      (node (ref "Q2") (pin "C") (pinfunction "C_C") (pintype "passive"))
    )
  )
)
